# PushButtonAction_4017.net
KiCad netlist of a schematic drawn in EAGLE
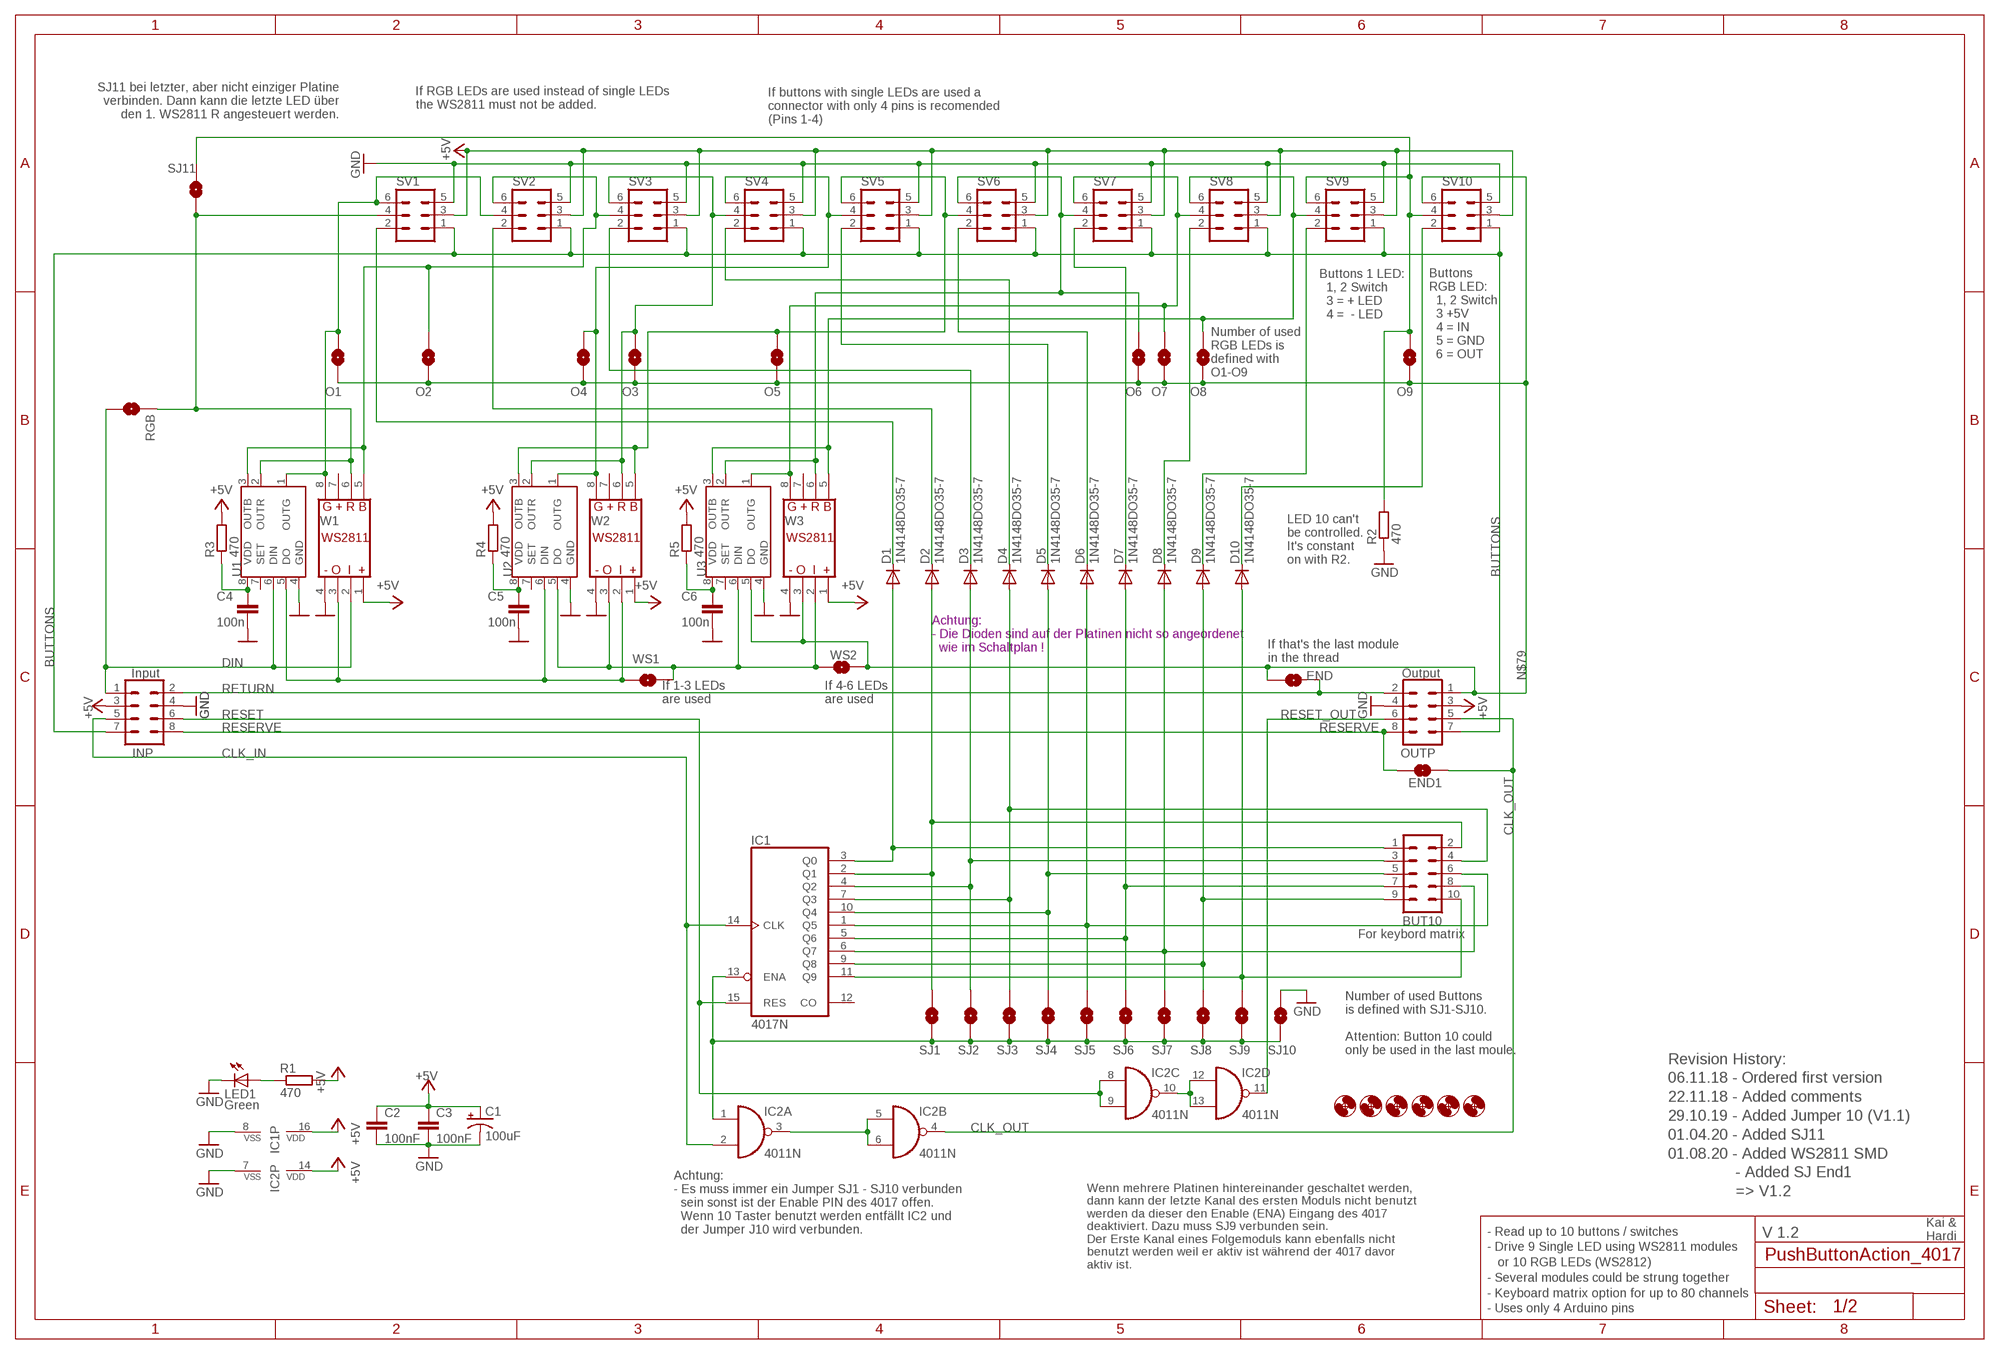
[diagram p0: schematic, sheet 1]
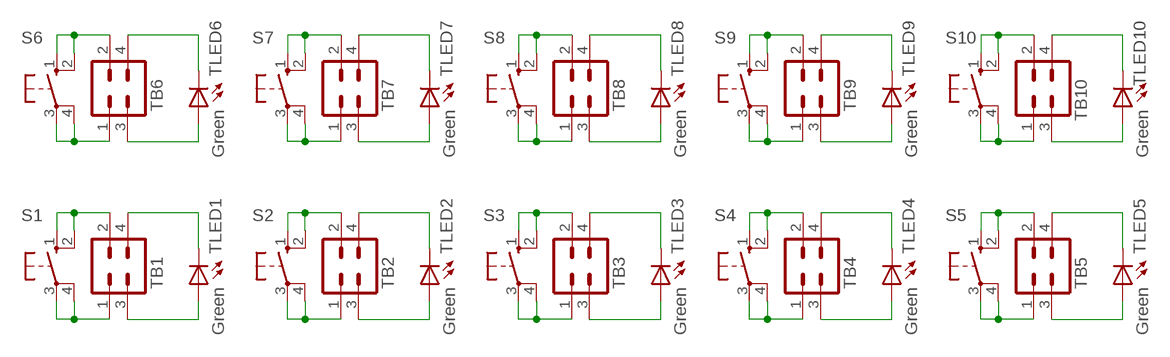
[diagram p1: schematic, sheet 2]

(export (version "E")
  (design (tool "Eeschema 10.0.6"))
  (components
    (comp (ref "BUT10")
      (value "CON-HARTING-ML_ML10")
      (footprint "eagle-import:CON-HARTING-ML_ML10")
      (libsource (lib "eagle-import") (part "CON-HARTING-ML_ML10"))
    )
    (comp (ref "C1")
      (value "100uF")
      (footprint "eagle-import:CPOL-RADIAL-100UF-25V")
      (libsource (lib "eagle-import") (part "100UF-25V-20%(PTH)"))
    )
    (comp (ref "C2")
      (value "100nF")
      (footprint "eagle-import:CAP-PTH-SMALL-KIT")
      (libsource (lib "eagle-import") (part "0.1UF-50V-20%(PTH)KIT-EZ"))
    )
    (comp (ref "C3")
      (value "100nF")
      (footprint "eagle-import:CAP-PTH-SMALL-KIT")
      (libsource (lib "eagle-import") (part "0.1UF-50V-20%(PTH)KIT-EZ"))
    )
    (comp (ref "C4")
      (value "100n")
      (footprint "eagle-import:C025-024X044")
      (libsource (lib "eagle-import") (part "C-EU025-024X044"))
    )
    (comp (ref "C5")
      (value "100n")
      (footprint "eagle-import:C025-024X044")
      (libsource (lib "eagle-import") (part "C-EU025-024X044"))
    )
    (comp (ref "C6")
      (value "100n")
      (footprint "eagle-import:C025-024X044")
      (libsource (lib "eagle-import") (part "C-EU025-024X044"))
    )
    (comp (ref "D1")
      (value "1N4148DO35-7")
      (footprint "eagle-import:DO35-7")
      (libsource (lib "eagle-import") (part "1N4148DO35-7"))
    )
    (comp (ref "D2")
      (value "1N4148DO35-7")
      (footprint "eagle-import:DO35-7")
      (libsource (lib "eagle-import") (part "1N4148DO35-7"))
    )
    (comp (ref "D3")
      (value "1N4148DO35-7")
      (footprint "eagle-import:DO35-7")
      (libsource (lib "eagle-import") (part "1N4148DO35-7"))
    )
    (comp (ref "D4")
      (value "1N4148DO35-7")
      (footprint "eagle-import:DO35-7")
      (libsource (lib "eagle-import") (part "1N4148DO35-7"))
    )
    (comp (ref "D5")
      (value "1N4148DO35-7")
      (footprint "eagle-import:DO35-7")
      (libsource (lib "eagle-import") (part "1N4148DO35-7"))
    )
    (comp (ref "D6")
      (value "1N4148DO35-7")
      (footprint "eagle-import:DO35-7")
      (libsource (lib "eagle-import") (part "1N4148DO35-7"))
    )
    (comp (ref "D7")
      (value "1N4148DO35-7")
      (footprint "eagle-import:DO35-7")
      (libsource (lib "eagle-import") (part "1N4148DO35-7"))
    )
    (comp (ref "D8")
      (value "1N4148DO35-7")
      (footprint "eagle-import:DO35-7")
      (libsource (lib "eagle-import") (part "1N4148DO35-7"))
    )
    (comp (ref "D9")
      (value "1N4148DO35-7")
      (footprint "eagle-import:DO35-7")
      (libsource (lib "eagle-import") (part "1N4148DO35-7"))
    )
    (comp (ref "D10")
      (value "1N4148DO35-7")
      (footprint "eagle-import:DO35-7")
      (libsource (lib "eagle-import") (part "1N4148DO35-7"))
    )
    (comp (ref "END")
      (value "SOLDERJUMPERNO")
      (footprint "eagle-import:SJ_2S-NO")
      (libsource (lib "eagle-import") (part "SOLDERJUMPERNO"))
    )
    (comp (ref "END1")
      (value "SOLDERJUMPERNO")
      (footprint "eagle-import:SJ_2S-NO")
      (libsource (lib "eagle-import") (part "SOLDERJUMPERNO"))
    )
    (comp (ref "H1")
      (value "MOUNT-HOLE3.0")
      (footprint "eagle-import:3,0")
      (libsource (lib "eagle-import") (part "MOUNT-HOLE3.0"))
    )
    (comp (ref "H2")
      (value "MOUNT-HOLE3.0")
      (footprint "eagle-import:3,0")
      (libsource (lib "eagle-import") (part "MOUNT-HOLE3.0"))
    )
    (comp (ref "H3")
      (value "MOUNT-HOLE3.0")
      (footprint "eagle-import:3,0")
      (libsource (lib "eagle-import") (part "MOUNT-HOLE3.0"))
    )
    (comp (ref "H4")
      (value "MOUNT-HOLE3.0")
      (footprint "eagle-import:3,0")
      (libsource (lib "eagle-import") (part "MOUNT-HOLE3.0"))
    )
    (comp (ref "H5")
      (value "MOUNT-HOLE3.0")
      (footprint "eagle-import:3,0")
      (libsource (lib "eagle-import") (part "MOUNT-HOLE3.0"))
    )
    (comp (ref "H6")
      (value "MOUNT-HOLE3.0")
      (footprint "eagle-import:3,0")
      (libsource (lib "eagle-import") (part "MOUNT-HOLE3.0"))
    )
    (comp (ref "IC1")
      (value "4017N")
      (footprint "eagle-import:DIL16")
      (libsource (lib "eagle-import") (part "4017N"))
    )
    (comp (ref "IC2")
      (value "4011N")
      (footprint "eagle-import:DIL14")
      (fields (field (name "SPICEPREFIX") "J"))
      (libsource (lib "eagle-import") (part "4011N"))
    )
    (comp (ref "INP")
      (value "CON-HARTING-ML_ML08")
      (footprint "eagle-import:CON-HARTING-ML_ML08")
      (libsource (lib "eagle-import") (part "CON-HARTING-ML_ML08"))
    )
    (comp (ref "LED1")
      (value "Green")
      (footprint "eagle-import:LED3MM")
      (libsource (lib "eagle-import") (part "LED3MM"))
    )
    (comp (ref "O1")
      (value "SOLDERJUMPERNO")
      (footprint "eagle-import:SJ_2S-NO")
      (libsource (lib "eagle-import") (part "SOLDERJUMPERNO"))
    )
    (comp (ref "O2")
      (value "SOLDERJUMPERNO")
      (footprint "eagle-import:SJ_2S-NO")
      (libsource (lib "eagle-import") (part "SOLDERJUMPERNO"))
    )
    (comp (ref "O3")
      (value "SOLDERJUMPERNO")
      (footprint "eagle-import:SJ_2S-NO")
      (libsource (lib "eagle-import") (part "SOLDERJUMPERNO"))
    )
    (comp (ref "O4")
      (value "SOLDERJUMPERNO")
      (footprint "eagle-import:SJ_2S-NO")
      (libsource (lib "eagle-import") (part "SOLDERJUMPERNO"))
    )
    (comp (ref "O5")
      (value "SOLDERJUMPERNO")
      (footprint "eagle-import:SJ_2S-NO")
      (libsource (lib "eagle-import") (part "SOLDERJUMPERNO"))
    )
    (comp (ref "O6")
      (value "SOLDERJUMPERNO")
      (footprint "eagle-import:SJ_2S-NO")
      (libsource (lib "eagle-import") (part "SOLDERJUMPERNO"))
    )
    (comp (ref "O7")
      (value "SOLDERJUMPERNO")
      (footprint "eagle-import:SJ_2S-NO")
      (libsource (lib "eagle-import") (part "SOLDERJUMPERNO"))
    )
    (comp (ref "O8")
      (value "SOLDERJUMPERNO")
      (footprint "eagle-import:SJ_2S-NO")
      (libsource (lib "eagle-import") (part "SOLDERJUMPERNO"))
    )
    (comp (ref "O9")
      (value "SOLDERJUMPERNO")
      (footprint "eagle-import:SJ_2S-NO")
      (libsource (lib "eagle-import") (part "SOLDERJUMPERNO"))
    )
    (comp (ref "OUTP")
      (value "CON-HARTING-ML_ML08")
      (footprint "eagle-import:CON-HARTING-ML_ML08")
      (libsource (lib "eagle-import") (part "CON-HARTING-ML_ML08"))
    )
    (comp (ref "R1")
      (value "470")
      (footprint "eagle-import:0207_2V")
      (libsource (lib "eagle-import") (part "R-EU_0207/2V"))
    )
    (comp (ref "R2")
      (value "470")
      (footprint "eagle-import:0204_5")
      (libsource (lib "eagle-import") (part "R-EU_0204/5"))
    )
    (comp (ref "R3")
      (value "470")
      (footprint "eagle-import:0207_2V")
      (libsource (lib "eagle-import") (part "R-EU_0207/2V"))
    )
    (comp (ref "R4")
      (value "470")
      (footprint "eagle-import:0207_2V")
      (libsource (lib "eagle-import") (part "R-EU_0207/2V"))
    )
    (comp (ref "R5")
      (value "470")
      (footprint "eagle-import:0207_2V")
      (libsource (lib "eagle-import") (part "R-EU_0207/2V"))
    )
    (comp (ref "RGB")
      (value "SOLDERJUMPERNO")
      (footprint "eagle-import:SJ_2S-NO")
      (libsource (lib "eagle-import") (part "SOLDERJUMPERNO"))
    )
    (comp (ref "SJ1")
      (value "SOLDERJUMPERNO")
      (footprint "eagle-import:SJ_2S-NO")
      (libsource (lib "eagle-import") (part "SOLDERJUMPERNO"))
    )
    (comp (ref "SJ2")
      (value "SOLDERJUMPERNO")
      (footprint "eagle-import:SJ_2S-NO")
      (libsource (lib "eagle-import") (part "SOLDERJUMPERNO"))
    )
    (comp (ref "SJ3")
      (value "SOLDERJUMPERNO")
      (footprint "eagle-import:SJ_2S-NO")
      (libsource (lib "eagle-import") (part "SOLDERJUMPERNO"))
    )
    (comp (ref "SJ4")
      (value "SOLDERJUMPERNO")
      (footprint "eagle-import:SJ_2S-NO")
      (libsource (lib "eagle-import") (part "SOLDERJUMPERNO"))
    )
    (comp (ref "SJ5")
      (value "SOLDERJUMPERNO")
      (footprint "eagle-import:SJ_2S-NO")
      (libsource (lib "eagle-import") (part "SOLDERJUMPERNO"))
    )
    (comp (ref "SJ6")
      (value "SOLDERJUMPERNO")
      (footprint "eagle-import:SJ_2S-NO")
      (libsource (lib "eagle-import") (part "SOLDERJUMPERNO"))
    )
    (comp (ref "SJ7")
      (value "SOLDERJUMPERNO")
      (footprint "eagle-import:SJ_2S-NO")
      (libsource (lib "eagle-import") (part "SOLDERJUMPERNO"))
    )
    (comp (ref "SJ8")
      (value "SOLDERJUMPERNO")
      (footprint "eagle-import:SJ_2S-NO")
      (libsource (lib "eagle-import") (part "SOLDERJUMPERNO"))
    )
    (comp (ref "SJ9")
      (value "SOLDERJUMPERNO")
      (footprint "eagle-import:SJ_2S-NO")
      (libsource (lib "eagle-import") (part "SOLDERJUMPERNO"))
    )
    (comp (ref "SJ10")
      (value "SOLDERJUMPERNO")
      (footprint "eagle-import:SJ_2S-NO")
      (libsource (lib "eagle-import") (part "SOLDERJUMPERNO"))
    )
    (comp (ref "SJ11")
      (value "SOLDERJUMPERNO")
      (footprint "eagle-import:SJ_2S-NO")
      (libsource (lib "eagle-import") (part "SOLDERJUMPERNO"))
    )
    (comp (ref "SV1")
      (value "CON-HARTING-ML_ML6")
      (footprint "eagle-import:CON-HARTING-ML_ML6")
      (libsource (lib "eagle-import") (part "CON-HARTING-ML_ML6"))
    )
    (comp (ref "SV2")
      (value "CON-HARTING-ML_ML6")
      (footprint "eagle-import:CON-HARTING-ML_ML6")
      (libsource (lib "eagle-import") (part "CON-HARTING-ML_ML6"))
    )
    (comp (ref "SV3")
      (value "CON-HARTING-ML_ML6")
      (footprint "eagle-import:CON-HARTING-ML_ML6")
      (libsource (lib "eagle-import") (part "CON-HARTING-ML_ML6"))
    )
    (comp (ref "SV4")
      (value "CON-HARTING-ML_ML6")
      (footprint "eagle-import:CON-HARTING-ML_ML6")
      (libsource (lib "eagle-import") (part "CON-HARTING-ML_ML6"))
    )
    (comp (ref "SV5")
      (value "CON-HARTING-ML_ML6")
      (footprint "eagle-import:CON-HARTING-ML_ML6")
      (libsource (lib "eagle-import") (part "CON-HARTING-ML_ML6"))
    )
    (comp (ref "SV6")
      (value "CON-HARTING-ML_ML6")
      (footprint "eagle-import:CON-HARTING-ML_ML6")
      (libsource (lib "eagle-import") (part "CON-HARTING-ML_ML6"))
    )
    (comp (ref "SV7")
      (value "CON-HARTING-ML_ML6")
      (footprint "eagle-import:CON-HARTING-ML_ML6")
      (libsource (lib "eagle-import") (part "CON-HARTING-ML_ML6"))
    )
    (comp (ref "SV8")
      (value "CON-HARTING-ML_ML6")
      (footprint "eagle-import:CON-HARTING-ML_ML6")
      (libsource (lib "eagle-import") (part "CON-HARTING-ML_ML6"))
    )
    (comp (ref "SV9")
      (value "CON-HARTING-ML_ML6")
      (footprint "eagle-import:CON-HARTING-ML_ML6")
      (libsource (lib "eagle-import") (part "CON-HARTING-ML_ML6"))
    )
    (comp (ref "SV10")
      (value "CON-HARTING-ML_ML6")
      (footprint "eagle-import:CON-HARTING-ML_ML6")
      (libsource (lib "eagle-import") (part "CON-HARTING-ML_ML6"))
    )
    (comp (ref "U1")
      (value "S3PO_MODUL_WS2811_SOUND_MP3-TF-16P_WS2811_AND_ATTINY_WS2811-ICSOP8")
      (footprint "eagle-import:SOP8")
      (libsource (lib "eagle-import") (part "S3PO_MODUL_WS2811_SOUND_MP3-TF-16P_WS2811_AND_ATTINY_WS2811-ICSOP8"))
    )
    (comp (ref "U2")
      (value "S3PO_MODUL_WS2811_SOUND_MP3-TF-16P_WS2811_AND_ATTINY_WS2811-ICSOP8")
      (footprint "eagle-import:SOP8")
      (libsource (lib "eagle-import") (part "S3PO_MODUL_WS2811_SOUND_MP3-TF-16P_WS2811_AND_ATTINY_WS2811-ICSOP8"))
    )
    (comp (ref "U3")
      (value "S3PO_MODUL_WS2811_SOUND_MP3-TF-16P_WS2811_AND_ATTINY_WS2811-ICSOP8")
      (footprint "eagle-import:SOP8")
      (libsource (lib "eagle-import") (part "S3PO_MODUL_WS2811_SOUND_MP3-TF-16P_WS2811_AND_ATTINY_WS2811-ICSOP8"))
    )
    (comp (ref "W1")
      (value "WS28115V")
      (footprint "eagle-import:WS2811_WS2811_5V")
      (libsource (lib "eagle-import") (part "WS28115V"))
    )
    (comp (ref "W2")
      (value "WS28115V")
      (footprint "eagle-import:WS2811_WS2811_5V")
      (libsource (lib "eagle-import") (part "WS28115V"))
    )
    (comp (ref "W3")
      (value "WS28115V")
      (footprint "eagle-import:WS2811_WS2811_5V")
      (libsource (lib "eagle-import") (part "WS28115V"))
    )
    (comp (ref "WS1")
      (value "SOLDERJUMPERNO")
      (footprint "eagle-import:SJ_2S-NO")
      (libsource (lib "eagle-import") (part "SOLDERJUMPERNO"))
    )
    (comp (ref "WS2")
      (value "SOLDERJUMPERNO")
      (footprint "eagle-import:SJ_2S-NO")
      (libsource (lib "eagle-import") (part "SOLDERJUMPERNO"))
    )
    (comp (ref "S1")
      (value "10-XX")
      (footprint "eagle-import:B3F-10XX")
      (fields (field (name "MPN") "B3F-1000"))
      (libsource (lib "eagle-import") (part "10-XX"))
    )
    (comp (ref "S2")
      (value "10-XX")
      (footprint "eagle-import:B3F-10XX")
      (fields (field (name "MPN") "B3F-1000"))
      (libsource (lib "eagle-import") (part "10-XX"))
    )
    (comp (ref "S3")
      (value "10-XX")
      (footprint "eagle-import:B3F-10XX")
      (fields (field (name "MPN") "B3F-1000"))
      (libsource (lib "eagle-import") (part "10-XX"))
    )
    (comp (ref "S4")
      (value "10-XX")
      (footprint "eagle-import:B3F-10XX")
      (fields (field (name "MPN") "B3F-1000"))
      (libsource (lib "eagle-import") (part "10-XX"))
    )
    (comp (ref "S5")
      (value "10-XX")
      (footprint "eagle-import:B3F-10XX")
      (fields (field (name "MPN") "B3F-1000"))
      (libsource (lib "eagle-import") (part "10-XX"))
    )
    (comp (ref "S6")
      (value "10-XX")
      (footprint "eagle-import:B3F-10XX")
      (fields (field (name "MPN") "B3F-1000"))
      (libsource (lib "eagle-import") (part "10-XX"))
    )
    (comp (ref "S7")
      (value "10-XX")
      (footprint "eagle-import:B3F-10XX")
      (fields (field (name "MPN") "B3F-1000"))
      (libsource (lib "eagle-import") (part "10-XX"))
    )
    (comp (ref "S8")
      (value "10-XX")
      (footprint "eagle-import:B3F-10XX")
      (fields (field (name "MPN") "B3F-1000"))
      (libsource (lib "eagle-import") (part "10-XX"))
    )
    (comp (ref "S9")
      (value "10-XX")
      (footprint "eagle-import:B3F-10XX")
      (fields (field (name "MPN") "B3F-1000"))
      (libsource (lib "eagle-import") (part "10-XX"))
    )
    (comp (ref "S10")
      (value "10-XX")
      (footprint "eagle-import:B3F-10XX")
      (fields (field (name "MPN") "B3F-1000"))
      (libsource (lib "eagle-import") (part "10-XX"))
    )
    (comp (ref "TB1")
      (value "CON-HARTING-ML_ML4ML4_FEMALE")
      (footprint "eagle-import:ML_ML4_FEMALE")
      (libsource (lib "eagle-import") (part "CON-HARTING-ML_ML4ML4_FEMALE"))
    )
    (comp (ref "TB2")
      (value "CON-HARTING-ML_ML4ML4_FEMALE")
      (footprint "eagle-import:ML_ML4_FEMALE")
      (libsource (lib "eagle-import") (part "CON-HARTING-ML_ML4ML4_FEMALE"))
    )
    (comp (ref "TB3")
      (value "CON-HARTING-ML_ML4ML4_FEMALE")
      (footprint "eagle-import:ML_ML4_FEMALE")
      (libsource (lib "eagle-import") (part "CON-HARTING-ML_ML4ML4_FEMALE"))
    )
    (comp (ref "TB4")
      (value "CON-HARTING-ML_ML4ML4_FEMALE")
      (footprint "eagle-import:ML_ML4_FEMALE")
      (libsource (lib "eagle-import") (part "CON-HARTING-ML_ML4ML4_FEMALE"))
    )
    (comp (ref "TB5")
      (value "CON-HARTING-ML_ML4ML4_FEMALE")
      (footprint "eagle-import:ML_ML4_FEMALE")
      (libsource (lib "eagle-import") (part "CON-HARTING-ML_ML4ML4_FEMALE"))
    )
    (comp (ref "TB6")
      (value "CON-HARTING-ML_ML4ML4_FEMALE")
      (footprint "eagle-import:ML_ML4_FEMALE")
      (libsource (lib "eagle-import") (part "CON-HARTING-ML_ML4ML4_FEMALE"))
    )
    (comp (ref "TB7")
      (value "CON-HARTING-ML_ML4ML4_FEMALE")
      (footprint "eagle-import:ML_ML4_FEMALE")
      (libsource (lib "eagle-import") (part "CON-HARTING-ML_ML4ML4_FEMALE"))
    )
    (comp (ref "TB8")
      (value "CON-HARTING-ML_ML4ML4_FEMALE")
      (footprint "eagle-import:ML_ML4_FEMALE")
      (libsource (lib "eagle-import") (part "CON-HARTING-ML_ML4ML4_FEMALE"))
    )
    (comp (ref "TB9")
      (value "CON-HARTING-ML_ML4ML4_FEMALE")
      (footprint "eagle-import:ML_ML4_FEMALE")
      (libsource (lib "eagle-import") (part "CON-HARTING-ML_ML4ML4_FEMALE"))
    )
    (comp (ref "TB10")
      (value "CON-HARTING-ML_ML4ML4_FEMALE")
      (footprint "eagle-import:ML_ML4_FEMALE")
      (libsource (lib "eagle-import") (part "CON-HARTING-ML_ML4ML4_FEMALE"))
    )
    (comp (ref "TLED1")
      (value "Green")
      (footprint "eagle-import:LED_LED3MM")
      (libsource (lib "eagle-import") (part "LED_LED3MM"))
    )
    (comp (ref "TLED2")
      (value "Green")
      (footprint "eagle-import:LED_LED3MM")
      (libsource (lib "eagle-import") (part "LED_LED3MM"))
    )
    (comp (ref "TLED3")
      (value "Green")
      (footprint "eagle-import:LED_LED3MM")
      (libsource (lib "eagle-import") (part "LED_LED3MM"))
    )
    (comp (ref "TLED4")
      (value "Green")
      (footprint "eagle-import:LED_LED3MM")
      (libsource (lib "eagle-import") (part "LED_LED3MM"))
    )
    (comp (ref "TLED5")
      (value "Green")
      (footprint "eagle-import:LED_LED3MM")
      (libsource (lib "eagle-import") (part "LED_LED3MM"))
    )
    (comp (ref "TLED6")
      (value "Green")
      (footprint "eagle-import:LED_LED3MM")
      (libsource (lib "eagle-import") (part "LED_LED3MM"))
    )
    (comp (ref "TLED7")
      (value "Green")
      (footprint "eagle-import:LED_LED3MM")
      (libsource (lib "eagle-import") (part "LED_LED3MM"))
    )
    (comp (ref "TLED8")
      (value "Green")
      (footprint "eagle-import:LED_LED3MM")
      (libsource (lib "eagle-import") (part "LED_LED3MM"))
    )
    (comp (ref "TLED9")
      (value "Green")
      (footprint "eagle-import:LED_LED3MM")
      (libsource (lib "eagle-import") (part "LED_LED3MM"))
    )
    (comp (ref "TLED10")
      (value "Green")
      (footprint "eagle-import:LED_LED3MM")
      (libsource (lib "eagle-import") (part "LED_LED3MM"))
    )
  )
  (nets
    (net (code "1") (name "+5V") (class "Default")
      (node (ref "C1") (pin "1") (pinfunction "+_1") (pintype "passive"))
      (node (ref "C2") (pin "1") (pinfunction "1_1") (pintype "passive"))
      (node (ref "C3") (pin "1") (pinfunction "1_1") (pintype "passive"))
      (node (ref "IC1") (pin "16") (pinfunction "VDD_16") (pintype "power_in"))
      (node (ref "IC2") (pin "14") (pinfunction "VDD_14") (pintype "power_in"))
      (node (ref "INP") (pin "3") (pinfunction "3_3") (pintype "passive"))
      (node (ref "OUTP") (pin "3") (pinfunction "3_3") (pintype "passive"))
      (node (ref "R1") (pin "2") (pinfunction "2_2") (pintype "passive"))
      (node (ref "R3") (pin "2") (pinfunction "2_2") (pintype "passive"))
      (node (ref "R4") (pin "2") (pinfunction "2_2") (pintype "passive"))
      (node (ref "R5") (pin "2") (pinfunction "2_2") (pintype "passive"))
      (node (ref "SV1") (pin "3") (pinfunction "3_3") (pintype "passive"))
      (node (ref "SV10") (pin "3") (pinfunction "3_3") (pintype "passive"))
      (node (ref "SV2") (pin "3") (pinfunction "3_3") (pintype "passive"))
      (node (ref "SV3") (pin "3") (pinfunction "3_3") (pintype "passive"))
      (node (ref "SV4") (pin "3") (pinfunction "3_3") (pintype "passive"))
      (node (ref "SV5") (pin "3") (pinfunction "3_3") (pintype "passive"))
      (node (ref "SV6") (pin "3") (pinfunction "3_3") (pintype "passive"))
      (node (ref "SV7") (pin "3") (pinfunction "3_3") (pintype "passive"))
      (node (ref "SV8") (pin "3") (pinfunction "3_3") (pintype "passive"))
      (node (ref "SV9") (pin "3") (pinfunction "3_3") (pintype "passive"))
      (node (ref "W1") (pin "1") (pinfunction "1_1") (pintype "passive"))
      (node (ref "W2") (pin "1") (pinfunction "1_1") (pintype "passive"))
      (node (ref "W3") (pin "1") (pinfunction "1_1") (pintype "passive"))
    )
    (net (code "2") (name "BUTTONS") (class "Default")
      (node (ref "INP") (pin "7") (pinfunction "7_7") (pintype "passive"))
      (node (ref "OUTP") (pin "7") (pinfunction "7_7") (pintype "passive"))
      (node (ref "SV1") (pin "1") (pinfunction "1_1") (pintype "passive"))
      (node (ref "SV10") (pin "1") (pinfunction "1_1") (pintype "passive"))
      (node (ref "SV2") (pin "1") (pinfunction "1_1") (pintype "passive"))
      (node (ref "SV3") (pin "1") (pinfunction "1_1") (pintype "passive"))
      (node (ref "SV4") (pin "1") (pinfunction "1_1") (pintype "passive"))
      (node (ref "SV5") (pin "1") (pinfunction "1_1") (pintype "passive"))
      (node (ref "SV6") (pin "1") (pinfunction "1_1") (pintype "passive"))
      (node (ref "SV7") (pin "1") (pinfunction "1_1") (pintype "passive"))
      (node (ref "SV8") (pin "1") (pinfunction "1_1") (pintype "passive"))
      (node (ref "SV9") (pin "1") (pinfunction "1_1") (pintype "passive"))
    )
    (net (code "3") (name "CLK_IN") (class "Default")
      (node (ref "IC1") (pin "14") (pinfunction "CLK_14") (pintype "input"))
      (node (ref "IC2") (pin "2") (pinfunction "I1_2") (pintype "input"))
      (node (ref "INP") (pin "5") (pinfunction "5_5") (pintype "passive"))
    )
    (net (code "4") (name "CLK_OUT") (class "Default")
      (node (ref "END1") (pin "1") (pinfunction "1_1") (pintype "passive"))
      (node (ref "IC2") (pin "4") (pinfunction "O_4") (pintype "output"))
      (node (ref "OUTP") (pin "5") (pinfunction "5_5") (pintype "passive"))
    )
    (net (code "5") (name "DIN") (class "Default")
      (node (ref "INP") (pin "1") (pinfunction "1_1") (pintype "passive"))
      (node (ref "RGB") (pin "1") (pinfunction "1_1") (pintype "passive"))
      (node (ref "U1") (pin "6") (pinfunction "DIN_6") (pintype "input"))
      (node (ref "W1") (pin "2") (pinfunction "2_2") (pintype "passive"))
    )
    (net (code "6") (name "GND") (class "Default")
      (node (ref "C1") (pin "2") (pinfunction "-_2") (pintype "passive"))
      (node (ref "C2") (pin "2") (pinfunction "2_2") (pintype "passive"))
      (node (ref "C3") (pin "2") (pinfunction "2_2") (pintype "passive"))
      (node (ref "C4") (pin "2") (pinfunction "2_2") (pintype "passive"))
      (node (ref "C5") (pin "2") (pinfunction "2_2") (pintype "passive"))
      (node (ref "C6") (pin "2") (pinfunction "2_2") (pintype "passive"))
      (node (ref "IC1") (pin "8") (pinfunction "VSS_8") (pintype "power_in"))
      (node (ref "IC2") (pin "7") (pinfunction "VSS_7") (pintype "power_in"))
      (node (ref "INP") (pin "4") (pinfunction "4_4") (pintype "passive"))
      (node (ref "LED1") (pin "K") (pinfunction "C_K") (pintype "passive"))
      (node (ref "OUTP") (pin "4") (pinfunction "4_4") (pintype "passive"))
      (node (ref "R2") (pin "1") (pinfunction "1_1") (pintype "passive"))
      (node (ref "SJ10") (pin "2") (pinfunction "2_2") (pintype "passive"))
      (node (ref "SV1") (pin "5") (pinfunction "5_5") (pintype "passive"))
      (node (ref "SV10") (pin "5") (pinfunction "5_5") (pintype "passive"))
      (node (ref "SV2") (pin "5") (pinfunction "5_5") (pintype "passive"))
      (node (ref "SV3") (pin "5") (pinfunction "5_5") (pintype "passive"))
      (node (ref "SV4") (pin "5") (pinfunction "5_5") (pintype "passive"))
      (node (ref "SV5") (pin "5") (pinfunction "5_5") (pintype "passive"))
      (node (ref "SV6") (pin "5") (pinfunction "5_5") (pintype "passive"))
      (node (ref "SV7") (pin "5") (pinfunction "5_5") (pintype "passive"))
      (node (ref "SV8") (pin "5") (pinfunction "5_5") (pintype "passive"))
      (node (ref "SV9") (pin "5") (pinfunction "5_5") (pintype "passive"))
      (node (ref "U1") (pin "4") (pinfunction "GND_4") (pintype "power_in"))
      (node (ref "U2") (pin "4") (pinfunction "GND_4") (pintype "power_in"))
      (node (ref "U3") (pin "4") (pinfunction "GND_4") (pintype "power_in"))
      (node (ref "W1") (pin "4") (pinfunction "4_4") (pintype "passive"))
      (node (ref "W2") (pin "4") (pinfunction "4_4") (pintype "passive"))
      (node (ref "W3") (pin "4") (pinfunction "4_4") (pintype "passive"))
    )
    (net (code "7") (name "N$79") (class "Default")
      (node (ref "END") (pin "2") (pinfunction "2_2") (pintype "passive"))
      (node (ref "O1") (pin "1") (pinfunction "1_1") (pintype "passive"))
      (node (ref "O2") (pin "1") (pinfunction "1_1") (pintype "passive"))
      (node (ref "O3") (pin "1") (pinfunction "1_1") (pintype "passive"))
      (node (ref "O4") (pin "1") (pinfunction "1_1") (pintype "passive"))
      (node (ref "O5") (pin "1") (pinfunction "1_1") (pintype "passive"))
      (node (ref "O6") (pin "1") (pinfunction "1_1") (pintype "passive"))
      (node (ref "O7") (pin "1") (pinfunction "1_1") (pintype "passive"))
      (node (ref "O8") (pin "1") (pinfunction "1_1") (pintype "passive"))
      (node (ref "O9") (pin "1") (pinfunction "1_1") (pintype "passive"))
      (node (ref "OUTP") (pin "1") (pinfunction "1_1") (pintype "passive"))
      (node (ref "SV10") (pin "6") (pinfunction "6_6") (pintype "passive"))
      (node (ref "U3") (pin "5") (pinfunction "DO_5") (pintype "output"))
      (node (ref "W3") (pin "3") (pinfunction "3_3") (pintype "passive"))
      (node (ref "WS2") (pin "1") (pinfunction "1_1") (pintype "passive"))
    )
    (net (code "8") (name "Net-(D1-PadC)") (class "Default")
      (node (ref "D1") (pin "C") (pinfunction "C_C") (pintype "passive"))
      (node (ref "SV1") (pin "2") (pinfunction "2_2") (pintype "passive"))
    )
    (net (code "9") (name "Net-(D2-PadC)") (class "Default")
      (node (ref "D2") (pin "C") (pinfunction "C_C") (pintype "passive"))
      (node (ref "SV2") (pin "2") (pinfunction "2_2") (pintype "passive"))
    )
    (net (code "10") (name "Net-(D3-PadC)") (class "Default")
      (node (ref "D3") (pin "C") (pinfunction "C_C") (pintype "passive"))
      (node (ref "SV3") (pin "2") (pinfunction "2_2") (pintype "passive"))
    )
    (net (code "11") (name "Net-(D4-PadC)") (class "Default")
      (node (ref "D4") (pin "C") (pinfunction "C_C") (pintype "passive"))
      (node (ref "SV4") (pin "2") (pinfunction "2_2") (pintype "passive"))
    )
    (net (code "12") (name "Net-(D5-PadC)") (class "Default")
      (node (ref "D5") (pin "C") (pinfunction "C_C") (pintype "passive"))
      (node (ref "SV5") (pin "2") (pinfunction "2_2") (pintype "passive"))
    )
    (net (code "13") (name "Net-(D6-PadC)") (class "Default")
      (node (ref "D6") (pin "C") (pinfunction "C_C") (pintype "passive"))
      (node (ref "SV6") (pin "2") (pinfunction "2_2") (pintype "passive"))
    )
    (net (code "14") (name "Net-(D7-PadC)") (class "Default")
      (node (ref "D7") (pin "C") (pinfunction "C_C") (pintype "passive"))
      (node (ref "SV7") (pin "2") (pinfunction "2_2") (pintype "passive"))
    )
    (net (code "15") (name "Net-(D8-PadC)") (class "Default")
      (node (ref "D8") (pin "C") (pinfunction "C_C") (pintype "passive"))
      (node (ref "SV8") (pin "2") (pinfunction "2_2") (pintype "passive"))
    )
    (net (code "16") (name "Net-(D9-PadC)") (class "Default")
      (node (ref "D9") (pin "C") (pinfunction "C_C") (pintype "passive"))
      (node (ref "SV9") (pin "2") (pinfunction "2_2") (pintype "passive"))
    )
    (net (code "17") (name "Net-(D10-PadC)") (class "Default")
      (node (ref "D10") (pin "C") (pinfunction "C_C") (pintype "passive"))
      (node (ref "SV10") (pin "2") (pinfunction "2_2") (pintype "passive"))
    )
    (net (code "18") (name "Net-(IC1A-ENA)") (class "Default")
      (node (ref "IC1") (pin "13") (pinfunction "ENA_13") (pintype "input"))
      (node (ref "IC2") (pin "1") (pinfunction "I0_1") (pintype "input"))
      (node (ref "SJ1") (pin "1") (pinfunction "1_1") (pintype "passive"))
      (node (ref "SJ10") (pin "1") (pinfunction "1_1") (pintype "passive"))
      (node (ref "SJ2") (pin "1") (pinfunction "1_1") (pintype "passive"))
      (node (ref "SJ3") (pin "1") (pinfunction "1_1") (pintype "passive"))
      (node (ref "SJ4") (pin "1") (pinfunction "1_1") (pintype "passive"))
      (node (ref "SJ5") (pin "1") (pinfunction "1_1") (pintype "passive"))
      (node (ref "SJ6") (pin "1") (pinfunction "1_1") (pintype "passive"))
      (node (ref "SJ7") (pin "1") (pinfunction "1_1") (pintype "passive"))
      (node (ref "SJ8") (pin "1") (pinfunction "1_1") (pintype "passive"))
      (node (ref "SJ9") (pin "1") (pinfunction "1_1") (pintype "passive"))
    )
    (net (code "19") (name "Net-(IC1A-Q0)") (class "Default")
      (node (ref "BUT10") (pin "1") (pinfunction "1_1") (pintype "passive"))
      (node (ref "D1") (pin "A") (pinfunction "A_A") (pintype "passive"))
      (node (ref "IC1") (pin "3") (pinfunction "Q0_3") (pintype "output"))
    )
    (net (code "20") (name "Net-(IC1A-Q1)") (class "Default")
      (node (ref "BUT10") (pin "2") (pinfunction "2_2") (pintype "passive"))
      (node (ref "D2") (pin "A") (pinfunction "A_A") (pintype "passive"))
      (node (ref "IC1") (pin "2") (pinfunction "Q1_2") (pintype "output"))
      (node (ref "SJ1") (pin "2") (pinfunction "2_2") (pintype "passive"))
    )
    (net (code "21") (name "Net-(IC1A-Q2)") (class "Default")
      (node (ref "BUT10") (pin "3") (pinfunction "3_3") (pintype "passive"))
      (node (ref "D3") (pin "A") (pinfunction "A_A") (pintype "passive"))
      (node (ref "IC1") (pin "4") (pinfunction "Q2_4") (pintype "output"))
      (node (ref "SJ2") (pin "2") (pinfunction "2_2") (pintype "passive"))
    )
    (net (code "22") (name "Net-(IC1A-Q3)") (class "Default")
      (node (ref "BUT10") (pin "4") (pinfunction "4_4") (pintype "passive"))
      (node (ref "D4") (pin "A") (pinfunction "A_A") (pintype "passive"))
      (node (ref "IC1") (pin "7") (pinfunction "Q3_7") (pintype "output"))
      (node (ref "SJ3") (pin "2") (pinfunction "2_2") (pintype "passive"))
    )
    (net (code "23") (name "Net-(IC1A-Q4)") (class "Default")
      (node (ref "BUT10") (pin "5") (pinfunction "5_5") (pintype "passive"))
      (node (ref "D5") (pin "A") (pinfunction "A_A") (pintype "passive"))
      (node (ref "IC1") (pin "10") (pinfunction "Q4_10") (pintype "output"))
      (node (ref "SJ4") (pin "2") (pinfunction "2_2") (pintype "passive"))
    )
    (net (code "24") (name "Net-(IC1A-Q5)") (class "Default")
      (node (ref "BUT10") (pin "6") (pinfunction "6_6") (pintype "passive"))
      (node (ref "D6") (pin "A") (pinfunction "A_A") (pintype "passive"))
      (node (ref "IC1") (pin "1") (pinfunction "Q5_1") (pintype "output"))
      (node (ref "SJ5") (pin "2") (pinfunction "2_2") (pintype "passive"))
    )
    (net (code "25") (name "Net-(IC1A-Q6)") (class "Default")
      (node (ref "BUT10") (pin "7") (pinfunction "7_7") (pintype "passive"))
      (node (ref "D7") (pin "A") (pinfunction "A_A") (pintype "passive"))
      (node (ref "IC1") (pin "5") (pinfunction "Q6_5") (pintype "output"))
      (node (ref "SJ6") (pin "2") (pinfunction "2_2") (pintype "passive"))
    )
    (net (code "26") (name "Net-(IC1A-Q7)") (class "Default")
      (node (ref "BUT10") (pin "8") (pinfunction "8_8") (pintype "passive"))
      (node (ref "D8") (pin "A") (pinfunction "A_A") (pintype "passive"))
      (node (ref "IC1") (pin "6") (pinfunction "Q7_6") (pintype "output"))
      (node (ref "SJ7") (pin "2") (pinfunction "2_2") (pintype "passive"))
    )
    (net (code "27") (name "Net-(IC1A-Q8)") (class "Default")
      (node (ref "BUT10") (pin "9") (pinfunction "9_9") (pintype "passive"))
      (node (ref "D9") (pin "A") (pinfunction "A_A") (pintype "passive"))
      (node (ref "IC1") (pin "9") (pinfunction "Q8_9") (pintype "output"))
      (node (ref "SJ8") (pin "2") (pinfunction "2_2") (pintype "passive"))
    )
    (net (code "28") (name "Net-(IC1A-Q9)") (class "Default")
      (node (ref "BUT10") (pin "10") (pinfunction "10_10") (pintype "passive"))
      (node (ref "D10") (pin "A") (pinfunction "A_A") (pintype "passive"))
      (node (ref "IC1") (pin "11") (pinfunction "Q9_11") (pintype "output"))
      (node (ref "SJ9") (pin "2") (pinfunction "2_2") (pintype "passive"))
    )
    (net (code "29") (name "Net-(IC2A-O)") (class "Default")
      (node (ref "IC2") (pin "3") (pinfunction "O_3") (pintype "output"))
      (node (ref "IC2") (pin "5") (pinfunction "I0_5") (pintype "input"))
      (node (ref "IC2") (pin "6") (pinfunction "I1_6") (pintype "input"))
    )
    (net (code "30") (name "Net-(IC2C-O)") (class "Default")
      (node (ref "IC2") (pin "10") (pinfunction "O_10") (pintype "output"))
      (node (ref "IC2") (pin "12") (pinfunction "I0_12") (pintype "input"))
      (node (ref "IC2") (pin "13") (pinfunction "I1_13") (pintype "input"))
    )
    (net (code "31") (name "Net-(LED1-PadA)") (class "Default")
      (node (ref "LED1") (pin "A") (pinfunction "A_A") (pintype "passive"))
      (node (ref "R1") (pin "1") (pinfunction "1_1") (pintype "passive"))
    )
    (net (code "32") (name "Net-(O9-Pad2)") (class "Default")
      (node (ref "O9") (pin "2") (pinfunction "2_2") (pintype "passive"))
      (node (ref "R2") (pin "2") (pinfunction "2_2") (pintype "passive"))
      (node (ref "SJ11") (pin "1") (pinfunction "1_1") (pintype "passive"))
      (node (ref "SV10") (pin "4") (pinfunction "4_4") (pintype "passive"))
      (node (ref "SV9") (pin "6") (pinfunction "6_6") (pintype "passive"))
    )
    (net (code "33") (name "Net-(S1-P)") (class "Default")
      (node (ref "S1") (pin "3") (pinfunction "P_3") (pintype "passive"))
      (node (ref "S1") (pin "4") (pinfunction "P1_4") (pintype "passive"))
      (node (ref "TB1") (pin "1") (pinfunction "1_1") (pintype "passive"))
    )
    (net (code "34") (name "Net-(S1-S)") (class "Default")
      (node (ref "S1") (pin "1") (pinfunction "S_1") (pintype "passive"))
      (node (ref "S1") (pin "2") (pinfunction "S1_2") (pintype "passive"))
      (node (ref "TB1") (pin "2") (pinfunction "2_2") (pintype "passive"))
    )
    (net (code "35") (name "Net-(S2-P)") (class "Default")
      (node (ref "S2") (pin "3") (pinfunction "P_3") (pintype "passive"))
      (node (ref "S2") (pin "4") (pinfunction "P1_4") (pintype "passive"))
      (node (ref "TB2") (pin "1") (pinfunction "1_1") (pintype "passive"))
    )
    (net (code "36") (name "Net-(S2-S)") (class "Default")
      (node (ref "S2") (pin "1") (pinfunction "S_1") (pintype "passive"))
      (node (ref "S2") (pin "2") (pinfunction "S1_2") (pintype "passive"))
      (node (ref "TB2") (pin "2") (pinfunction "2_2") (pintype "passive"))
    )
    (net (code "37") (name "Net-(S3-P)") (class "Default")
      (node (ref "S3") (pin "3") (pinfunction "P_3") (pintype "passive"))
      (node (ref "S3") (pin "4") (pinfunction "P1_4") (pintype "passive"))
      (node (ref "TB3") (pin "1") (pinfunction "1_1") (pintype "passive"))
    )
    (net (code "38") (name "Net-(S3-S)") (class "Default")
      (node (ref "S3") (pin "1") (pinfunction "S_1") (pintype "passive"))
      (node (ref "S3") (pin "2") (pinfunction "S1_2") (pintype "passive"))
      (node (ref "TB3") (pin "2") (pinfunction "2_2") (pintype "passive"))
    )
    (net (code "39") (name "Net-(S4-P)") (class "Default")
      (node (ref "S4") (pin "3") (pinfunction "P_3") (pintype "passive"))
      (node (ref "S4") (pin "4") (pinfunction "P1_4") (pintype "passive"))
      (node (ref "TB4") (pin "1") (pinfunction "1_1") (pintype "passive"))
    )
    (net (code "40") (name "Net-(S4-S)") (class "Default")
      (node (ref "S4") (pin "1") (pinfunction "S_1") (pintype "passive"))
      (node (ref "S4") (pin "2") (pinfunction "S1_2") (pintype "passive"))
      (node (ref "TB4") (pin "2") (pinfunction "2_2") (pintype "passive"))
    )
    (net (code "41") (name "Net-(S5-P)") (class "Default")
      (node (ref "S5") (pin "3") (pinfunction "P_3") (pintype "passive"))
      (node (ref "S5") (pin "4") (pinfunction "P1_4") (pintype "passive"))
      (node (ref "TB5") (pin "1") (pinfunction "1_1") (pintype "passive"))
    )
    (net (code "42") (name "Net-(S5-S)") (class "Default")
      (node (ref "S5") (pin "1") (pinfunction "S_1") (pintype "passive"))
      (node (ref "S5") (pin "2") (pinfunction "S1_2") (pintype "passive"))
      (node (ref "TB5") (pin "2") (pinfunction "2_2") (pintype "passive"))
    )
    (net (code "43") (name "Net-(S6-P)") (class "Default")
      (node (ref "S6") (pin "3") (pinfunction "P_3") (pintype "passive"))
      (node (ref "S6") (pin "4") (pinfunction "P1_4") (pintype "passive"))
      (node (ref "TB6") (pin "1") (pinfunction "1_1") (pintype "passive"))
    )
    (net (code "44") (name "Net-(S6-S)") (class "Default")
      (node (ref "S6") (pin "1") (pinfunction "S_1") (pintype "passive"))
      (node (ref "S6") (pin "2") (pinfunction "S1_2") (pintype "passive"))
      (node (ref "TB6") (pin "2") (pinfunction "2_2") (pintype "passive"))
    )
    (net (code "45") (name "Net-(S7-P)") (class "Default")
      (node (ref "S7") (pin "3") (pinfunction "P_3") (pintype "passive"))
      (node (ref "S7") (pin "4") (pinfunction "P1_4") (pintype "passive"))
      (node (ref "TB7") (pin "1") (pinfunction "1_1") (pintype "passive"))
    )
    (net (code "46") (name "Net-(S7-S)") (class "Default")
      (node (ref "S7") (pin "1") (pinfunction "S_1") (pintype "passive"))
      (node (ref "S7") (pin "2") (pinfunction "S1_2") (pintype "passive"))
      (node (ref "TB7") (pin "2") (pinfunction "2_2") (pintype "passive"))
    )
    (net (code "47") (name "Net-(S8-P)") (class "Default")
      (node (ref "S8") (pin "3") (pinfunction "P_3") (pintype "passive"))
      (node (ref "S8") (pin "4") (pinfunction "P1_4") (pintype "passive"))
      (node (ref "TB8") (pin "1") (pinfunction "1_1") (pintype "passive"))
    )
    (net (code "48") (name "Net-(S8-S)") (class "Default")
      (node (ref "S8") (pin "1") (pinfunction "S_1") (pintype "passive"))
      (node (ref "S8") (pin "2") (pinfunction "S1_2") (pintype "passive"))
      (node (ref "TB8") (pin "2") (pinfunction "2_2") (pintype "passive"))
    )
    (net (code "49") (name "Net-(S9-P)") (class "Default")
      (node (ref "S9") (pin "3") (pinfunction "P_3") (pintype "passive"))
      (node (ref "S9") (pin "4") (pinfunction "P1_4") (pintype "passive"))
      (node (ref "TB9") (pin "1") (pinfunction "1_1") (pintype "passive"))
    )
    (net (code "50") (name "Net-(S9-S)") (class "Default")
      (node (ref "S9") (pin "1") (pinfunction "S_1") (pintype "passive"))
      (node (ref "S9") (pin "2") (pinfunction "S1_2") (pintype "passive"))
      (node (ref "TB9") (pin "2") (pinfunction "2_2") (pintype "passive"))
    )
    (net (code "51") (name "Net-(S10-P)") (class "Default")
      (node (ref "S10") (pin "3") (pinfunction "P_3") (pintype "passive"))
      (node (ref "S10") (pin "4") (pinfunction "P1_4") (pintype "passive"))
      (node (ref "TB10") (pin "1") (pinfunction "1_1") (pintype "passive"))
    )
    (net (code "52") (name "Net-(S10-S)") (class "Default")
      (node (ref "S10") (pin "1") (pinfunction "S_1") (pintype "passive"))
      (node (ref "S10") (pin "2") (pinfunction "S1_2") (pintype "passive"))
      (node (ref "TB10") (pin "2") (pinfunction "2_2") (pintype "passive"))
    )
    (net (code "53") (name "Net-(TB1-Pad3)") (class "Default")
      (node (ref "TB1") (pin "3") (pinfunction "3_3") (pintype "passive"))
      (node (ref "TLED1") (pin "A") (pinfunction "A_A") (pintype "passive"))
    )
    (net (code "54") (name "Net-(TB2-Pad3)") (class "Default")
      (node (ref "TB2") (pin "3") (pinfunction "3_3") (pintype "passive"))
      (node (ref "TLED2") (pin "A") (pinfunction "A_A") (pintype "passive"))
    )
    (net (code "55") (name "Net-(TB3-Pad3)") (class "Default")
      (node (ref "TB3") (pin "3") (pinfunction "3_3") (pintype "passive"))
      (node (ref "TLED3") (pin "A") (pinfunction "A_A") (pintype "passive"))
    )
    (net (code "56") (name "Net-(TB4-Pad3)") (class "Default")
      (node (ref "TB4") (pin "3") (pinfunction "3_3") (pintype "passive"))
      (node (ref "TLED4") (pin "A") (pinfunction "A_A") (pintype "passive"))
    )
    (net (code "57") (name "Net-(TB5-Pad3)") (class "Default")
      (node (ref "TB5") (pin "3") (pinfunction "3_3") (pintype "passive"))
      (node (ref "TLED5") (pin "A") (pinfunction "A_A") (pintype "passive"))
    )
    (net (code "58") (name "Net-(TB6-Pad3)") (class "Default")
      (node (ref "TB6") (pin "3") (pinfunction "3_3") (pintype "passive"))
      (node (ref "TLED6") (pin "A") (pinfunction "A_A") (pintype "passive"))
    )
    (net (code "59") (name "Net-(TB7-Pad3)") (class "Default")
      (node (ref "TB7") (pin "3") (pinfunction "3_3") (pintype "passive"))
      (node (ref "TLED7") (pin "A") (pinfunction "A_A") (pintype "passive"))
    )
    (net (code "60") (name "Net-(TB8-Pad3)") (class "Default")
      (node (ref "TB8") (pin "3") (pinfunction "3_3") (pintype "passive"))
      (node (ref "TLED8") (pin "A") (pinfunction "A_A") (pintype "passive"))
    )
    (net (code "61") (name "Net-(TB9-Pad3)") (class "Default")
      (node (ref "TB9") (pin "3") (pinfunction "3_3") (pintype "passive"))
      (node (ref "TLED9") (pin "A") (pinfunction "A_A") (pintype "passive"))
    )
    (net (code "62") (name "Net-(TB10-Pad3)") (class "Default")
      (node (ref "TB10") (pin "3") (pinfunction "3_3") (pintype "passive"))
      (node (ref "TLED10") (pin "A") (pinfunction "A_A") (pintype "passive"))
    )
    (net (code "63") (name "Net-(TLED1-C)") (class "Default")
      (node (ref "TB1") (pin "4") (pinfunction "4_4") (pintype "passive"))
      (node (ref "TLED1") (pin "K") (pinfunction "C_K") (pintype "passive"))
    )
    (net (code "64") (name "Net-(TLED2-C)") (class "Default")
      (node (ref "TB2") (pin "4") (pinfunction "4_4") (pintype "passive"))
      (node (ref "TLED2") (pin "K") (pinfunction "C_K") (pintype "passive"))
    )
    (net (code "65") (name "Net-(TLED3-C)") (class "Default")
      (node (ref "TB3") (pin "4") (pinfunction "4_4") (pintype "passive"))
      (node (ref "TLED3") (pin "K") (pinfunction "C_K") (pintype "passive"))
    )
    (net (code "66") (name "Net-(TLED4-C)") (class "Default")
      (node (ref "TB4") (pin "4") (pinfunction "4_4") (pintype "passive"))
      (node (ref "TLED4") (pin "K") (pinfunction "C_K") (pintype "passive"))
    )
    (net (code "67") (name "Net-(TLED5-C)") (class "Default")
      (node (ref "TB5") (pin "4") (pinfunction "4_4") (pintype "passive"))
      (node (ref "TLED5") (pin "K") (pinfunction "C_K") (pintype "passive"))
    )
    (net (code "68") (name "Net-(TLED6-C)") (class "Default")
      (node (ref "TB6") (pin "4") (pinfunction "4_4") (pintype "passive"))
      (node (ref "TLED6") (pin "K") (pinfunction "C_K") (pintype "passive"))
    )
    (net (code "69") (name "Net-(TLED7-C)") (class "Default")
      (node (ref "TB7") (pin "4") (pinfunction "4_4") (pintype "passive"))
      (node (ref "TLED7") (pin "K") (pinfunction "C_K") (pintype "passive"))
    )
    (net (code "70") (name "Net-(TLED8-C)") (class "Default")
      (node (ref "TB8") (pin "4") (pinfunction "4_4") (pintype "passive"))
      (node (ref "TLED8") (pin "K") (pinfunction "C_K") (pintype "passive"))
    )
    (net (code "71") (name "Net-(TLED9-C)") (class "Default")
      (node (ref "TB9") (pin "4") (pinfunction "4_4") (pintype "passive"))
      (node (ref "TLED9") (pin "K") (pinfunction "C_K") (pintype "passive"))
    )
    (net (code "72") (name "Net-(TLED10-C)") (class "Default")
      (node (ref "TB10") (pin "4") (pinfunction "4_4") (pintype "passive"))
      (node (ref "TLED10") (pin "K") (pinfunction "C_K") (pintype "passive"))
    )
    (net (code "73") (name "Net-(U1-DO)") (class "Default")
      (node (ref "U1") (pin "5") (pinfunction "DO_5") (pintype "output"))
      (node (ref "U2") (pin "6") (pinfunction "DIN_6") (pintype "input"))
      (node (ref "W1") (pin "3") (pinfunction "3_3") (pintype "passive"))
      (node (ref "W2") (pin "2") (pinfunction "2_2") (pintype "passive"))
      (node (ref "WS1") (pin "1") (pinfunction "1_1") (pintype "passive"))
    )
    (net (code "74") (name "Net-(U1-OUTB)") (class "Default")
      (node (ref "O2") (pin "2") (pinfunction "2_2") (pintype "passive"))
      (node (ref "SV2") (pin "6") (pinfunction "6_6") (pintype "passive"))
      (node (ref "SV3") (pin "4") (pinfunction "4_4") (pintype "passive"))
      (node (ref "U1") (pin "3") (pinfunction "OUTB_3") (pintype "open_collector"))
      (node (ref "W1") (pin "5") (pinfunction "5_5") (pintype "passive"))
    )
    (net (code "75") (name "Net-(U1-OUTG)") (class "Default")
      (node (ref "O1") (pin "2") (pinfunction "2_2") (pintype "passive"))
      (node (ref "SV1") (pin "6") (pinfunction "6_6") (pintype "passive"))
      (node (ref "SV2") (pin "4") (pinfunction "4_4") (pintype "passive"))
      (node (ref "U1") (pin "1") (pinfunction "OUTG_1") (pintype "open_collector"))
      (node (ref "W1") (pin "8") (pinfunction "8_8") (pintype "passive"))
    )
    (net (code "76") (name "Net-(U1-OUTR)") (class "Default")
      (node (ref "RGB") (pin "2") (pinfunction "2_2") (pintype "passive"))
      (node (ref "SJ11") (pin "2") (pinfunction "2_2") (pintype "passive"))
      (node (ref "SV1") (pin "4") (pinfunction "4_4") (pintype "passive"))
      (node (ref "U1") (pin "2") (pinfunction "OUTR_2") (pintype "open_collector"))
      (node (ref "W1") (pin "6") (pinfunction "6_6") (pintype "passive"))
    )
    (net (code "77") (name "Net-(U1-VDD)") (class "Default")
      (node (ref "C4") (pin "1") (pinfunction "1_1") (pintype "passive"))
      (node (ref "R3") (pin "1") (pinfunction "1_1") (pintype "passive"))
      (node (ref "U1") (pin "8") (pinfunction "VDD_8") (pintype "power_in"))
    )
    (net (code "78") (name "Net-(U2-DO)") (class "Default")
      (node (ref "U2") (pin "5") (pinfunction "DO_5") (pintype "output"))
      (node (ref "U3") (pin "6") (pinfunction "DIN_6") (pintype "input"))
      (node (ref "W2") (pin "3") (pinfunction "3_3") (pintype "passive"))
      (node (ref "W3") (pin "2") (pinfunction "2_2") (pintype "passive"))
      (node (ref "WS1") (pin "2") (pinfunction "2_2") (pintype "passive"))
      (node (ref "WS2") (pin "2") (pinfunction "2_2") (pintype "passive"))
    )
    (net (code "79") (name "Net-(U2-OUTB)") (class "Default")
      (node (ref "O5") (pin "2") (pinfunction "2_2") (pintype "passive"))
      (node (ref "SV5") (pin "6") (pinfunction "6_6") (pintype "passive"))
      (node (ref "SV6") (pin "4") (pinfunction "4_4") (pintype "passive"))
      (node (ref "U2") (pin "3") (pinfunction "OUTB_3") (pintype "open_collector"))
      (node (ref "W2") (pin "5") (pinfunction "5_5") (pintype "passive"))
    )
    (net (code "80") (name "Net-(U2-OUTG)") (class "Default")
      (node (ref "O4") (pin "2") (pinfunction "2_2") (pintype "passive"))
      (node (ref "SV4") (pin "6") (pinfunction "6_6") (pintype "passive"))
      (node (ref "SV5") (pin "4") (pinfunction "4_4") (pintype "passive"))
      (node (ref "U2") (pin "1") (pinfunction "OUTG_1") (pintype "open_collector"))
      (node (ref "W2") (pin "8") (pinfunction "8_8") (pintype "passive"))
    )
    (net (code "81") (name "Net-(U2-OUTR)") (class "Default")
      (node (ref "O3") (pin "2") (pinfunction "2_2") (pintype "passive"))
      (node (ref "SV3") (pin "6") (pinfunction "6_6") (pintype "passive"))
      (node (ref "SV4") (pin "4") (pinfunction "4_4") (pintype "passive"))
      (node (ref "U2") (pin "2") (pinfunction "OUTR_2") (pintype "open_collector"))
      (node (ref "W2") (pin "6") (pinfunction "6_6") (pintype "passive"))
    )
    (net (code "82") (name "Net-(U2-VDD)") (class "Default")
      (node (ref "C5") (pin "1") (pinfunction "1_1") (pintype "passive"))
      (node (ref "R4") (pin "1") (pinfunction "1_1") (pintype "passive"))
      (node (ref "U2") (pin "8") (pinfunction "VDD_8") (pintype "power_in"))
    )
    (net (code "83") (name "Net-(U3-OUTB)") (class "Default")
      (node (ref "O8") (pin "2") (pinfunction "2_2") (pintype "passive"))
      (node (ref "SV8") (pin "6") (pinfunction "6_6") (pintype "passive"))
      (node (ref "SV9") (pin "4") (pinfunction "4_4") (pintype "passive"))
      (node (ref "U3") (pin "3") (pinfunction "OUTB_3") (pintype "open_collector"))
      (node (ref "W3") (pin "5") (pinfunction "5_5") (pintype "passive"))
    )
    (net (code "84") (name "Net-(U3-OUTG)") (class "Default")
      (node (ref "O7") (pin "2") (pinfunction "2_2") (pintype "passive"))
      (node (ref "SV7") (pin "6") (pinfunction "6_6") (pintype "passive"))
      (node (ref "SV8") (pin "4") (pinfunction "4_4") (pintype "passive"))
      (node (ref "U3") (pin "1") (pinfunction "OUTG_1") (pintype "open_collector"))
      (node (ref "W3") (pin "8") (pinfunction "8_8") (pintype "passive"))
    )
    (net (code "85") (name "Net-(U3-OUTR)") (class "Default")
      (node (ref "O6") (pin "2") (pinfunction "2_2") (pintype "passive"))
      (node (ref "SV6") (pin "6") (pinfunction "6_6") (pintype "passive"))
      (node (ref "SV7") (pin "4") (pinfunction "4_4") (pintype "passive"))
      (node (ref "U3") (pin "2") (pinfunction "OUTR_2") (pintype "open_collector"))
      (node (ref "W3") (pin "6") (pinfunction "6_6") (pintype "passive"))
    )
    (net (code "86") (name "Net-(U3-VDD)") (class "Default")
      (node (ref "C6") (pin "1") (pinfunction "1_1") (pintype "passive"))
      (node (ref "R5") (pin "1") (pinfunction "1_1") (pintype "passive"))
      (node (ref "U3") (pin "8") (pinfunction "VDD_8") (pintype "power_in"))
    )
    (net (code "87") (name "RESERVE") (class "Default")
      (node (ref "END1") (pin "2") (pinfunction "2_2") (pintype "passive"))
      (node (ref "INP") (pin "8") (pinfunction "8_8") (pintype "passive"))
      (node (ref "OUTP") (pin "8") (pinfunction "8_8") (pintype "passive"))
    )
    (net (code "88") (name "RESET") (class "Default")
      (node (ref "IC1") (pin "15") (pinfunction "RES_15") (pintype "input"))
      (node (ref "IC2") (pin "8") (pinfunction "I0_8") (pintype "input"))
      (node (ref "IC2") (pin "9") (pinfunction "I1_9") (pintype "input"))
      (node (ref "INP") (pin "6") (pinfunction "6_6") (pintype "passive"))
    )
    (net (code "89") (name "RESET_OUT") (class "Default")
      (node (ref "IC2") (pin "11") (pinfunction "O_11") (pintype "output"))
      (node (ref "OUTP") (pin "6") (pinfunction "6_6") (pintype "passive"))
    )
    (net (code "90") (name "RETURN") (class "Default")
      (node (ref "END") (pin "1") (pinfunction "1_1") (pintype "passive"))
      (node (ref "INP") (pin "2") (pinfunction "2_2") (pintype "passive"))
      (node (ref "OUTP") (pin "2") (pinfunction "2_2") (pintype "passive"))
    )
    (net (code "91") (name "unconnected-(IC1A-CO-Pad12)") (class "Default")
      (node (ref "IC1") (pin "12") (pinfunction "CO_12") (pintype "output"))
    )
    (net (code "92") (name "unconnected-(U1-SET-Pad7)") (class "Default")
      (node (ref "U1") (pin "7") (pinfunction "SET_7") (pintype "bidirectional"))
    )
    (net (code "93") (name "unconnected-(U2-SET-Pad7)") (class "Default")
      (node (ref "U2") (pin "7") (pinfunction "SET_7") (pintype "bidirectional"))
    )
    (net (code "94") (name "unconnected-(U3-SET-Pad7)") (class "Default")
      (node (ref "U3") (pin "7") (pinfunction "SET_7") (pintype "bidirectional"))
    )
    (net (code "95") (name "unconnected-(W1-Pad7)") (class "Default")
      (node (ref "W1") (pin "7") (pinfunction "7_7") (pintype "passive"))
    )
    (net (code "96") (name "unconnected-(W2-Pad7)") (class "Default")
      (node (ref "W2") (pin "7") (pinfunction "7_7") (pintype "passive"))
    )
    (net (code "97") (name "unconnected-(W3-Pad7)") (class "Default")
      (node (ref "W3") (pin "7") (pinfunction "7_7") (pintype "passive"))
    )
  )
)
